# usb_can.net
KiCad netlist of a schematic drawn in EAGLE
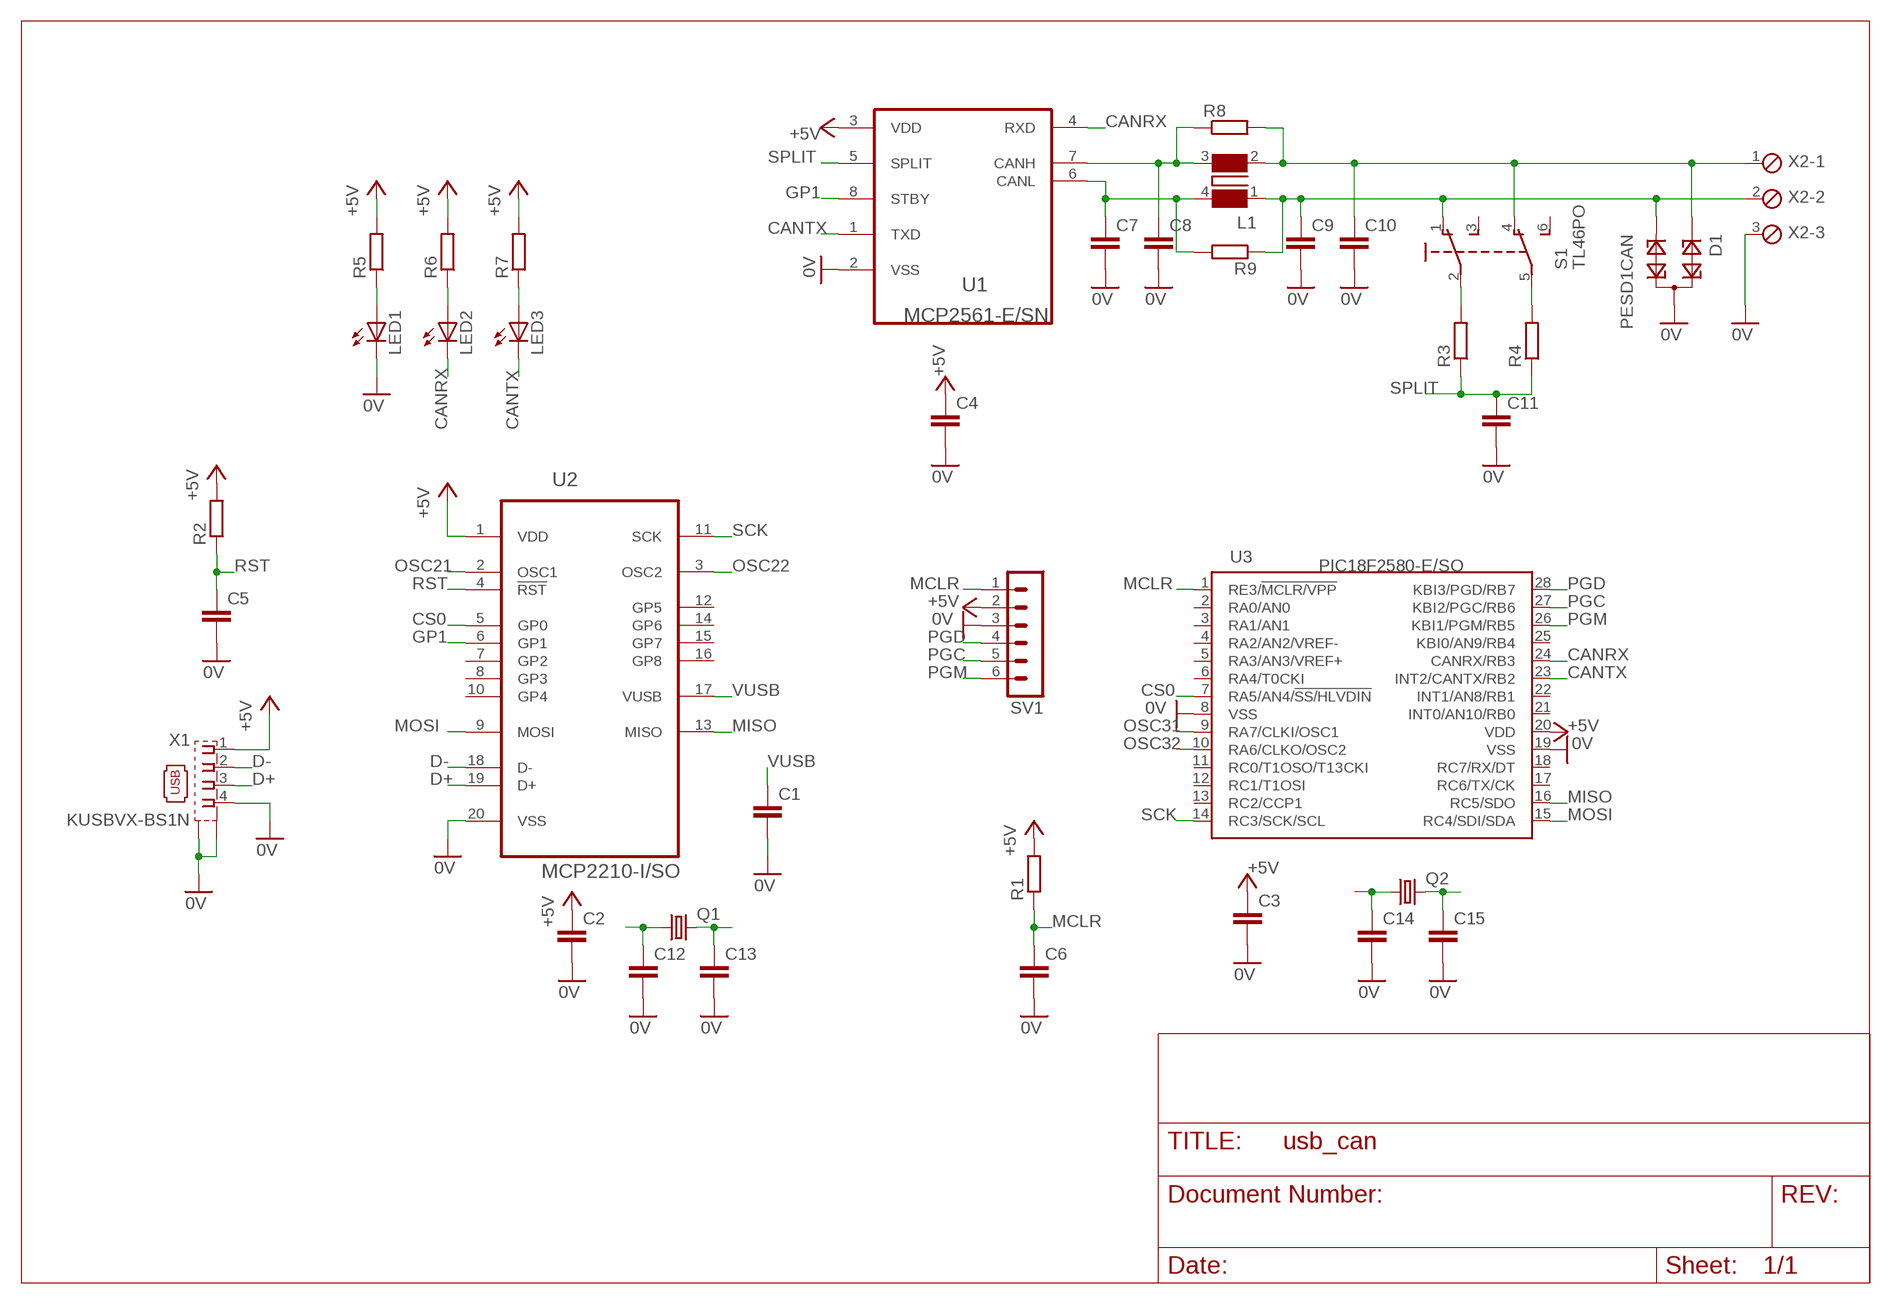
[diagram p0: schematic, sheet 1]

(export (version "E")
  (design (tool "Eeschema 10.0.6"))
  (components
    (comp (ref "C1")
      (value "C-EUC1210")
      (footprint "eagle-import:C1210")
      (libsource (lib "eagle-import") (part "C-EUC1210"))
    )
    (comp (ref "C2")
      (value "C-EUC0805")
      (footprint "eagle-import:C0805")
      (libsource (lib "eagle-import") (part "C-EUC0805"))
    )
    (comp (ref "C3")
      (value "C-EUC0805")
      (footprint "eagle-import:C0805")
      (libsource (lib "eagle-import") (part "C-EUC0805"))
    )
    (comp (ref "C4")
      (value "C-EUC0805")
      (footprint "eagle-import:C0805")
      (libsource (lib "eagle-import") (part "C-EUC0805"))
    )
    (comp (ref "C5")
      (value "C-EUC0805")
      (footprint "eagle-import:C0805")
      (libsource (lib "eagle-import") (part "C-EUC0805"))
    )
    (comp (ref "C6")
      (value "C-EUC0805")
      (footprint "eagle-import:C0805")
      (libsource (lib "eagle-import") (part "C-EUC0805"))
    )
    (comp (ref "C7")
      (value "C-EUC0805")
      (footprint "eagle-import:C0805")
      (libsource (lib "eagle-import") (part "C-EUC0805"))
    )
    (comp (ref "C8")
      (value "C-EUC0805")
      (footprint "eagle-import:C0805")
      (libsource (lib "eagle-import") (part "C-EUC0805"))
    )
    (comp (ref "C9")
      (value "C-EUC0805")
      (footprint "eagle-import:C0805")
      (libsource (lib "eagle-import") (part "C-EUC0805"))
    )
    (comp (ref "C10")
      (value "C-EUC0805")
      (footprint "eagle-import:C0805")
      (libsource (lib "eagle-import") (part "C-EUC0805"))
    )
    (comp (ref "C11")
      (value "C-EUC0805")
      (footprint "eagle-import:C0805")
      (libsource (lib "eagle-import") (part "C-EUC0805"))
    )
    (comp (ref "C12")
      (value "C-EUC0805")
      (footprint "eagle-import:C0805")
      (libsource (lib "eagle-import") (part "C-EUC0805"))
    )
    (comp (ref "C13")
      (value "C-EUC0805")
      (footprint "eagle-import:C0805")
      (libsource (lib "eagle-import") (part "C-EUC0805"))
    )
    (comp (ref "C14")
      (value "C-EUC0805")
      (footprint "eagle-import:C0805")
      (libsource (lib "eagle-import") (part "C-EUC0805"))
    )
    (comp (ref "C15")
      (value "C-EUC0805")
      (footprint "eagle-import:C0805")
      (libsource (lib "eagle-import") (part "C-EUC0805"))
    )
    (comp (ref "D1")
      (value "PESD1CAN")
      (footprint "eagle-import:SOT23")
      (libsource (lib "eagle-import") (part "PESD1CAN"))
    )
    (comp (ref "L1")
      (value "WE-SLM-744242510")
      (footprint "eagle-import:WE-SLM")
      (fields (field (name "MPN") "744242510"))
      (libsource (lib "eagle-import") (part "WE-SLM-744242510"))
    )
    (comp (ref "LED1")
      (value "LED3MM")
      (footprint "eagle-import:LED3MM")
      (libsource (lib "eagle-import") (part "LED3MM"))
    )
    (comp (ref "LED2")
      (value "LED3MM")
      (footprint "eagle-import:LED3MM")
      (libsource (lib "eagle-import") (part "LED3MM"))
    )
    (comp (ref "LED3")
      (value "LED3MM")
      (footprint "eagle-import:LED3MM")
      (libsource (lib "eagle-import") (part "LED3MM"))
    )
    (comp (ref "Q1")
      (value "CRYSTALHC49UP")
      (footprint "eagle-import:HC49UP")
      (libsource (lib "eagle-import") (part "CRYSTALHC49UP"))
    )
    (comp (ref "Q2")
      (value "CRYSTALHC49UP")
      (footprint "eagle-import:HC49UP")
      (libsource (lib "eagle-import") (part "CRYSTALHC49UP"))
    )
    (comp (ref "R1")
      (value "R-EU_R0805")
      (footprint "eagle-import:R0805")
      (libsource (lib "eagle-import") (part "R-EU_R0805"))
    )
    (comp (ref "R2")
      (value "R-EU_R0805")
      (footprint "eagle-import:R0805")
      (libsource (lib "eagle-import") (part "R-EU_R0805"))
    )
    (comp (ref "R3")
      (value "R-EU_MELF0204W")
      (footprint "eagle-import:MINI_MELF-0204W")
      (libsource (lib "eagle-import") (part "R-EU_MELF0204W"))
    )
    (comp (ref "R4")
      (value "R-EU_MELF0204W")
      (footprint "eagle-import:MINI_MELF-0204W")
      (libsource (lib "eagle-import") (part "R-EU_MELF0204W"))
    )
    (comp (ref "R5")
      (value "R-EU_R0805")
      (footprint "eagle-import:R0805")
      (libsource (lib "eagle-import") (part "R-EU_R0805"))
    )
    (comp (ref "R6")
      (value "R-EU_R0805")
      (footprint "eagle-import:R0805")
      (libsource (lib "eagle-import") (part "R-EU_R0805"))
    )
    (comp (ref "R7")
      (value "R-EU_R0805")
      (footprint "eagle-import:R0805")
      (libsource (lib "eagle-import") (part "R-EU_R0805"))
    )
    (comp (ref "R8")
      (value "R-EU_MELF0204W")
      (footprint "eagle-import:MINI_MELF-0204W")
      (libsource (lib "eagle-import") (part "R-EU_MELF0204W"))
    )
    (comp (ref "R9")
      (value "R-EU_MELF0204W")
      (footprint "eagle-import:MINI_MELF-0204W")
      (libsource (lib "eagle-import") (part "R-EU_MELF0204W"))
    )
    (comp (ref "S1")
      (value "TL46PO")
      (footprint "eagle-import:TL4XPO")
      (libsource (lib "eagle-import") (part "TL46PO"))
    )
    (comp (ref "SV1")
      (value "MA06-1")
      (footprint "eagle-import:MA06-1")
      (libsource (lib "eagle-import") (part "MA06-1"))
    )
    (comp (ref "U1")
      (value "MCP2561-E/SN")
      (footprint "eagle-import:SOIC127P600X175-8N")
      (libsource (lib "eagle-import") (part "MCP2561-E/SN"))
    )
    (comp (ref "U2")
      (value "MCP2210-I/SO")
      (footprint "eagle-import:SOIC127P1030X265-20N")
      (libsource (lib "eagle-import") (part "MCP2210-I/SO"))
    )
    (comp (ref "U3")
      (value "PIC18F2580-E/SO")
      (footprint "eagle-import:SO28W")
      (fields (field (name "MF") "MICROCHIP") (field (name "MPN") "PIC18F2580-I/SO"))
      (libsource (lib "eagle-import") (part "PIC18F280-E/SO5"))
    )
    (comp (ref "X1")
      (value "KUSBVX-BS1N")
      (footprint "eagle-import:KUSBVX-BS1N")
      (libsource (lib "eagle-import") (part "KUSBVX-BS1N"))
    )
    (comp (ref "X2")
      (value "MPT3")
      (footprint "eagle-import:3POL254")
      (libsource (lib "eagle-import") (part "MPT3"))
    )
  )
  (nets
    (net (code "1") (name "+5V") (class "Default")
      (node (ref "C2") (pin "1") (pinfunction "1_1") (pintype "passive"))
      (node (ref "C3") (pin "1") (pinfunction "1_1") (pintype "passive"))
      (node (ref "C4") (pin "1") (pinfunction "1_1") (pintype "passive"))
      (node (ref "R1") (pin "2") (pinfunction "2_2") (pintype "passive"))
      (node (ref "R2") (pin "2") (pinfunction "2_2") (pintype "passive"))
      (node (ref "R5") (pin "2") (pinfunction "2_2") (pintype "passive"))
      (node (ref "R6") (pin "2") (pinfunction "2_2") (pintype "passive"))
      (node (ref "R7") (pin "2") (pinfunction "2_2") (pintype "passive"))
      (node (ref "SV1") (pin "2") (pinfunction "2_2") (pintype "passive"))
      (node (ref "U1") (pin "3") (pinfunction "VDD_3") (pintype "power_in"))
      (node (ref "U2") (pin "1") (pinfunction "VDD_1") (pintype "power_in"))
      (node (ref "U3") (pin "20") (pinfunction "VDD_20") (pintype "power_in"))
      (node (ref "X1") (pin "1") (pinfunction "1_1") (pintype "passive"))
    )
    (net (code "2") (name "/CANRX") (class "Default")
      (node (ref "LED2") (pin "K") (pinfunction "C_K") (pintype "passive"))
      (node (ref "U1") (pin "4") (pinfunction "RXD_4") (pintype "output"))
      (node (ref "U3") (pin "24") (pinfunction "CANRX/RB3_24") (pintype "bidirectional"))
    )
    (net (code "3") (name "/CANTX") (class "Default")
      (node (ref "LED3") (pin "K") (pinfunction "C_K") (pintype "passive"))
      (node (ref "U1") (pin "1") (pinfunction "TXD_1") (pintype "input"))
      (node (ref "U3") (pin "23") (pinfunction "INT2/CANTX/RB2_23") (pintype "bidirectional"))
    )
    (net (code "4") (name "/CS0") (class "Default")
      (node (ref "U2") (pin "5") (pinfunction "GP0_5") (pintype "bidirectional"))
      (node (ref "U3") (pin "7") (pinfunction "RA5/AN4/~{SS/HLVDIN}_7") (pintype "bidirectional"))
    )
    (net (code "5") (name "/D+") (class "Default")
      (node (ref "U2") (pin "19") (pinfunction "D+_19") (pintype "passive"))
      (node (ref "X1") (pin "3") (pinfunction "3_3") (pintype "passive"))
    )
    (net (code "6") (name "/D-") (class "Default")
      (node (ref "U2") (pin "18") (pinfunction "D-_18") (pintype "passive"))
      (node (ref "X1") (pin "2") (pinfunction "2_2") (pintype "passive"))
    )
    (net (code "7") (name "/GP1") (class "Default")
      (node (ref "U1") (pin "8") (pinfunction "STBY_8") (pintype "input"))
      (node (ref "U2") (pin "6") (pinfunction "GP1_6") (pintype "bidirectional"))
    )
    (net (code "8") (name "/MCLR") (class "Default")
      (node (ref "C6") (pin "1") (pinfunction "1_1") (pintype "passive"))
      (node (ref "R1") (pin "1") (pinfunction "1_1") (pintype "passive"))
      (node (ref "SV1") (pin "1") (pinfunction "1_1") (pintype "passive"))
      (node (ref "U3") (pin "1") (pinfunction "RE3/~{MCLR/VPP}_1") (pintype "input"))
    )
    (net (code "9") (name "/MISO") (class "Default")
      (node (ref "U2") (pin "13") (pinfunction "MISO_13") (pintype "output"))
      (node (ref "U3") (pin "16") (pinfunction "RC5/SDO_16") (pintype "bidirectional"))
    )
    (net (code "10") (name "/MOSI") (class "Default")
      (node (ref "U2") (pin "9") (pinfunction "MOSI_9") (pintype "input"))
      (node (ref "U3") (pin "15") (pinfunction "RC4/SDI/SDA_15") (pintype "bidirectional"))
    )
    (net (code "11") (name "/OSC21") (class "Default")
      (node (ref "C12") (pin "1") (pinfunction "1_1") (pintype "passive"))
      (node (ref "Q1") (pin "1") (pinfunction "1_1") (pintype "passive"))
      (node (ref "U2") (pin "2") (pinfunction "OSC1_2") (pintype "input"))
    )
    (net (code "12") (name "/OSC22") (class "Default")
      (node (ref "C13") (pin "1") (pinfunction "1_1") (pintype "passive"))
      (node (ref "Q1") (pin "2") (pinfunction "2_2") (pintype "passive"))
      (node (ref "U2") (pin "3") (pinfunction "OSC2_3") (pintype "output"))
    )
    (net (code "13") (name "/OSC31") (class "Default")
      (node (ref "C14") (pin "1") (pinfunction "1_1") (pintype "passive"))
      (node (ref "Q2") (pin "1") (pinfunction "1_1") (pintype "passive"))
      (node (ref "U3") (pin "9") (pinfunction "RA7/CLKI/OSC1_9") (pintype "input"))
    )
    (net (code "14") (name "/OSC32") (class "Default")
      (node (ref "C15") (pin "1") (pinfunction "1_1") (pintype "passive"))
      (node (ref "Q2") (pin "2") (pinfunction "2_2") (pintype "passive"))
      (node (ref "U3") (pin "10") (pinfunction "RA6/CLKO/OSC2_10") (pintype "output"))
    )
    (net (code "15") (name "/PGC") (class "Default")
      (node (ref "SV1") (pin "5") (pinfunction "5_5") (pintype "passive"))
      (node (ref "U3") (pin "27") (pinfunction "KBI2/PGC/RB6_27") (pintype "bidirectional"))
    )
    (net (code "16") (name "/PGD") (class "Default")
      (node (ref "SV1") (pin "4") (pinfunction "4_4") (pintype "passive"))
      (node (ref "U3") (pin "28") (pinfunction "KBI3/PGD/RB7_28") (pintype "bidirectional"))
    )
    (net (code "17") (name "/PGM") (class "Default")
      (node (ref "SV1") (pin "6") (pinfunction "6_6") (pintype "passive"))
      (node (ref "U3") (pin "26") (pinfunction "KBI1/PGM/RB5_26") (pintype "bidirectional"))
    )
    (net (code "18") (name "/RST") (class "Default")
      (node (ref "C5") (pin "1") (pinfunction "1_1") (pintype "passive"))
      (node (ref "R2") (pin "1") (pinfunction "1_1") (pintype "passive"))
      (node (ref "U2") (pin "4") (pinfunction "~{RST}_4") (pintype "input"))
    )
    (net (code "19") (name "/SCK") (class "Default")
      (node (ref "U2") (pin "11") (pinfunction "SCK_11") (pintype "output"))
      (node (ref "U3") (pin "14") (pinfunction "RC3/SCK/SCL_14") (pintype "bidirectional"))
    )
    (net (code "20") (name "/SPLIT") (class "Default")
      (node (ref "C11") (pin "1") (pinfunction "1_1") (pintype "passive"))
      (node (ref "R3") (pin "1") (pinfunction "1_1") (pintype "passive"))
      (node (ref "R4") (pin "1") (pinfunction "1_1") (pintype "passive"))
      (node (ref "U1") (pin "5") (pinfunction "SPLIT_5") (pintype "passive"))
    )
    (net (code "21") (name "/VUSB") (class "Default")
      (node (ref "C1") (pin "1") (pinfunction "1_1") (pintype "passive"))
      (node (ref "U2") (pin "17") (pinfunction "VUSB_17") (pintype "output"))
    )
    (net (code "22") (name "0V") (class "Default")
      (node (ref "C1") (pin "2") (pinfunction "2_2") (pintype "passive"))
      (node (ref "C10") (pin "2") (pinfunction "2_2") (pintype "passive"))
      (node (ref "C11") (pin "2") (pinfunction "2_2") (pintype "passive"))
      (node (ref "C12") (pin "2") (pinfunction "2_2") (pintype "passive"))
      (node (ref "C13") (pin "2") (pinfunction "2_2") (pintype "passive"))
      (node (ref "C14") (pin "2") (pinfunction "2_2") (pintype "passive"))
      (node (ref "C15") (pin "2") (pinfunction "2_2") (pintype "passive"))
      (node (ref "C2") (pin "2") (pinfunction "2_2") (pintype "passive"))
      (node (ref "C3") (pin "2") (pinfunction "2_2") (pintype "passive"))
      (node (ref "C4") (pin "2") (pinfunction "2_2") (pintype "passive"))
      (node (ref "C5") (pin "2") (pinfunction "2_2") (pintype "passive"))
      (node (ref "C6") (pin "2") (pinfunction "2_2") (pintype "passive"))
      (node (ref "C7") (pin "2") (pinfunction "2_2") (pintype "passive"))
      (node (ref "C8") (pin "2") (pinfunction "2_2") (pintype "passive"))
      (node (ref "C9") (pin "2") (pinfunction "2_2") (pintype "passive"))
      (node (ref "D1") (pin "3") (pinfunction "3_3") (pintype "passive"))
      (node (ref "LED1") (pin "K") (pinfunction "C_K") (pintype "passive"))
      (node (ref "SV1") (pin "3") (pinfunction "3_3") (pintype "passive"))
      (node (ref "U1") (pin "2") (pinfunction "VSS_2") (pintype "power_in"))
      (node (ref "U2") (pin "20") (pinfunction "VSS_20") (pintype "passive"))
      (node (ref "U3") (pin "19") (pinfunction "VSS_19") (pintype "power_in"))
      (node (ref "U3") (pin "8") (pinfunction "VSS_8") (pintype "power_in"))
      (node (ref "X1") (pin "4") (pinfunction "4_4") (pintype "passive"))
      (node (ref "X1") (pin "M1") (pinfunction "S1_M1") (pintype "passive"))
      (node (ref "X1") (pin "M2") (pinfunction "S2_M2") (pintype "passive"))
      (node (ref "X2") (pin "3") (pinfunction "1_3") (pintype "passive"))
    )
    (net (code "23") (name "Net-(L1-1)") (class "Default")
      (node (ref "C10") (pin "1") (pinfunction "1_1") (pintype "passive"))
      (node (ref "D1") (pin "1") (pinfunction "1_1") (pintype "passive"))
      (node (ref "L1") (pin "2") (pinfunction "1_2") (pintype "passive"))
      (node (ref "R8") (pin "2") (pinfunction "2_2") (pintype "passive"))
      (node (ref "S1") (pin "4") (pinfunction "O1_4") (pintype "passive"))
      (node (ref "X2") (pin "1") (pinfunction "1_1") (pintype "passive"))
    )
    (net (code "24") (name "Net-(L1-2)") (class "Default")
      (node (ref "C8") (pin "1") (pinfunction "1_1") (pintype "passive"))
      (node (ref "L1") (pin "3") (pinfunction "2_3") (pintype "passive"))
      (node (ref "R8") (pin "1") (pinfunction "1_1") (pintype "passive"))
      (node (ref "U1") (pin "7") (pinfunction "CANH_7") (pintype "bidirectional"))
    )
    (net (code "25") (name "Net-(L1-3)") (class "Default")
      (node (ref "C9") (pin "1") (pinfunction "1_1") (pintype "passive"))
      (node (ref "D1") (pin "2") (pinfunction "2_2") (pintype "passive"))
      (node (ref "L1") (pin "1") (pinfunction "3_1") (pintype "passive"))
      (node (ref "R9") (pin "1") (pinfunction "1_1") (pintype "passive"))
      (node (ref "S1") (pin "1") (pinfunction "O_1") (pintype "passive"))
      (node (ref "X2") (pin "2") (pinfunction "1_2") (pintype "passive"))
    )
    (net (code "26") (name "Net-(LED1-PadA)") (class "Default")
      (node (ref "LED1") (pin "A") (pinfunction "A_A") (pintype "passive"))
      (node (ref "R5") (pin "1") (pinfunction "1_1") (pintype "passive"))
    )
    (net (code "27") (name "Net-(LED2-PadA)") (class "Default")
      (node (ref "LED2") (pin "A") (pinfunction "A_A") (pintype "passive"))
      (node (ref "R6") (pin "1") (pinfunction "1_1") (pintype "passive"))
    )
    (net (code "28") (name "Net-(LED3-PadA)") (class "Default")
      (node (ref "LED3") (pin "A") (pinfunction "A_A") (pintype "passive"))
      (node (ref "R7") (pin "1") (pinfunction "1_1") (pintype "passive"))
    )
    (net (code "29") (name "Net-(S1-P)") (class "Default")
      (node (ref "R3") (pin "2") (pinfunction "2_2") (pintype "passive"))
      (node (ref "S1") (pin "2") (pinfunction "P_2") (pintype "passive"))
    )
    (net (code "30") (name "Net-(S1-P1)") (class "Default")
      (node (ref "R4") (pin "2") (pinfunction "2_2") (pintype "passive"))
      (node (ref "S1") (pin "5") (pinfunction "P1_5") (pintype "passive"))
    )
    (net (code "31") (name "Net-(U1-CANL)") (class "Default")
      (node (ref "C7") (pin "1") (pinfunction "1_1") (pintype "passive"))
      (node (ref "L1") (pin "4") (pinfunction "4_4") (pintype "passive"))
      (node (ref "R9") (pin "2") (pinfunction "2_2") (pintype "passive"))
      (node (ref "U1") (pin "6") (pinfunction "CANL_6") (pintype "bidirectional"))
    )
    (net (code "32") (name "unconnected-(S1-S-Pad3)") (class "Default")
      (node (ref "S1") (pin "3") (pinfunction "S_3") (pintype "passive"))
    )
    (net (code "33") (name "unconnected-(S1-S1-Pad6)") (class "Default")
      (node (ref "S1") (pin "6") (pinfunction "S1_6") (pintype "passive"))
    )
    (net (code "34") (name "unconnected-(U2-GP2-Pad7)") (class "Default")
      (node (ref "U2") (pin "7") (pinfunction "GP2_7") (pintype "bidirectional"))
    )
    (net (code "35") (name "unconnected-(U2-GP3-Pad8)") (class "Default")
      (node (ref "U2") (pin "8") (pinfunction "GP3_8") (pintype "bidirectional"))
    )
    (net (code "36") (name "unconnected-(U2-GP4-Pad10)") (class "Default")
      (node (ref "U2") (pin "10") (pinfunction "GP4_10") (pintype "bidirectional"))
    )
    (net (code "37") (name "unconnected-(U2-GP5-Pad12)") (class "Default")
      (node (ref "U2") (pin "12") (pinfunction "GP5_12") (pintype "bidirectional"))
    )
    (net (code "38") (name "unconnected-(U2-GP6-Pad14)") (class "Default")
      (node (ref "U2") (pin "14") (pinfunction "GP6_14") (pintype "bidirectional"))
    )
    (net (code "39") (name "unconnected-(U2-GP7-Pad15)") (class "Default")
      (node (ref "U2") (pin "15") (pinfunction "GP7_15") (pintype "bidirectional"))
    )
    (net (code "40") (name "unconnected-(U2-GP8-Pad16)") (class "Default")
      (node (ref "U2") (pin "16") (pinfunction "GP8_16") (pintype "bidirectional"))
    )
    (net (code "41") (name "unconnected-(U3-INT0{slash}AN10{slash}RB0-Pad21)") (class "Default")
      (node (ref "U3") (pin "21") (pinfunction "INT0/AN10/RB0_21") (pintype "bidirectional"))
    )
    (net (code "42") (name "unconnected-(U3-INT1{slash}AN8{slash}RB1-Pad22)") (class "Default")
      (node (ref "U3") (pin "22") (pinfunction "INT1/AN8/RB1_22") (pintype "bidirectional"))
    )
    (net (code "43") (name "unconnected-(U3-KBI0{slash}AN9{slash}RB4-Pad25)") (class "Default")
      (node (ref "U3") (pin "25") (pinfunction "KBI0/AN9/RB4_25") (pintype "bidirectional"))
    )
    (net (code "44") (name "unconnected-(U3-RA0{slash}AN0-Pad2)") (class "Default")
      (node (ref "U3") (pin "2") (pinfunction "RA0/AN0_2") (pintype "bidirectional"))
    )
    (net (code "45") (name "unconnected-(U3-RA1{slash}AN1-Pad3)") (class "Default")
      (node (ref "U3") (pin "3") (pinfunction "RA1/AN1_3") (pintype "bidirectional"))
    )
    (net (code "46") (name "unconnected-(U3-RA2{slash}AN2{slash}VREF--Pad4)") (class "Default")
      (node (ref "U3") (pin "4") (pinfunction "RA2/AN2/VREF-_4") (pintype "bidirectional"))
    )
    (net (code "47") (name "unconnected-(U3-RA3{slash}AN3{slash}VREF+-Pad5)") (class "Default")
      (node (ref "U3") (pin "5") (pinfunction "RA3/AN3/VREF+_5") (pintype "bidirectional"))
    )
    (net (code "48") (name "unconnected-(U3-RA4{slash}T0CKI-Pad6)") (class "Default")
      (node (ref "U3") (pin "6") (pinfunction "RA4/T0CKI_6") (pintype "bidirectional"))
    )
    (net (code "49") (name "unconnected-(U3-RC0{slash}T1OSO{slash}T13CKI-Pad11)") (class "Default")
      (node (ref "U3") (pin "11") (pinfunction "RC0/T1OSO/T13CKI_11") (pintype "bidirectional"))
    )
    (net (code "50") (name "unconnected-(U3-RC1{slash}T1OSI-Pad12)") (class "Default")
      (node (ref "U3") (pin "12") (pinfunction "RC1/T1OSI_12") (pintype "bidirectional"))
    )
    (net (code "51") (name "unconnected-(U3-RC2{slash}CCP1-Pad13)") (class "Default")
      (node (ref "U3") (pin "13") (pinfunction "RC2/CCP1_13") (pintype "bidirectional"))
    )
    (net (code "52") (name "unconnected-(U3-RC6{slash}TX{slash}CK-Pad17)") (class "Default")
      (node (ref "U3") (pin "17") (pinfunction "RC6/TX/CK_17") (pintype "bidirectional"))
    )
    (net (code "53") (name "unconnected-(U3-RC7{slash}RX{slash}DT-Pad18)") (class "Default")
      (node (ref "U3") (pin "18") (pinfunction "RC7/RX/DT_18") (pintype "bidirectional"))
    )
  )
)
